# lp_board.net
KiCad netlist of a schematic drawn in EAGLE
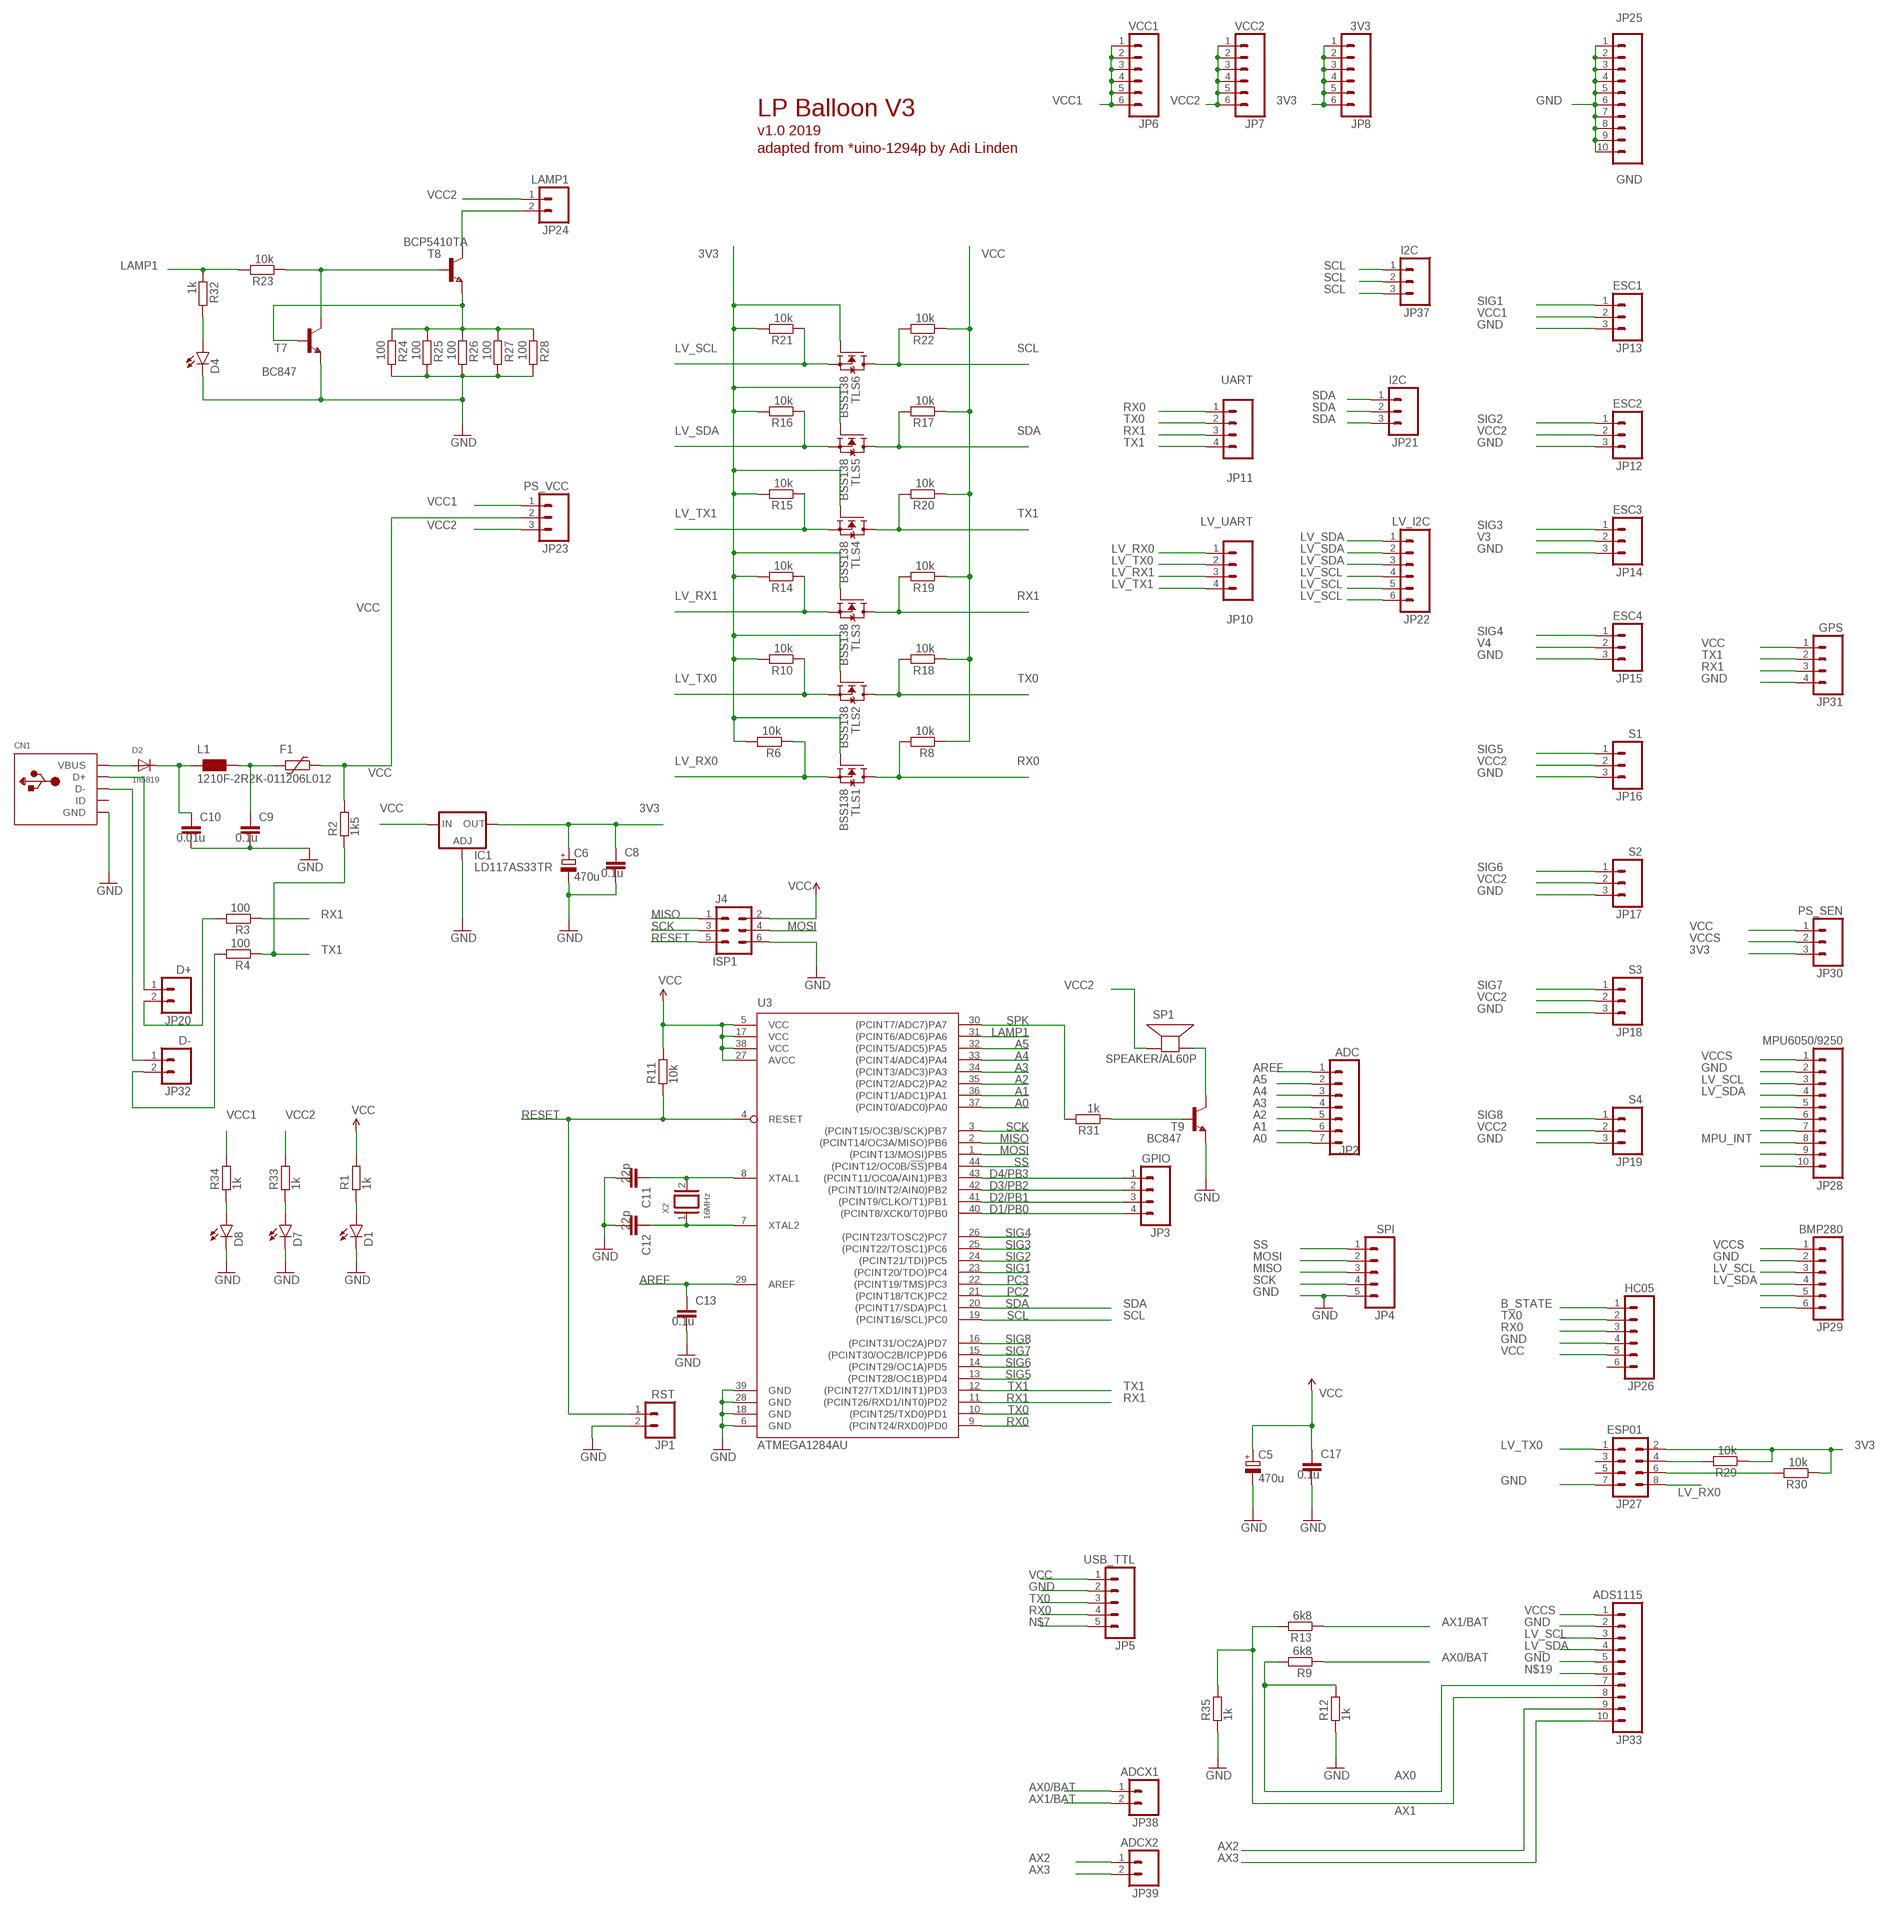
[diagram p0: schematic, sheet 1]

(export (version "E")
  (design (tool "Eeschema 10.0.6"))
  (components
    (comp (ref "C5")
      (value "470u")
      (footprint "eagle-import:E5-10,5")
      (libsource (lib "eagle-import") (part "CPOL-EUE5-10.5"))
    )
    (comp (ref "C6")
      (value "470u")
      (footprint "eagle-import:E5-10,5")
      (libsource (lib "eagle-import") (part "CPOL-EUE5-10.5"))
    )
    (comp (ref "C8")
      (value "0.1u")
      (footprint "eagle-import:C0603")
      (libsource (lib "eagle-import") (part "C-EUC0603"))
    )
    (comp (ref "C9")
      (value "0.1u")
      (footprint "eagle-import:C0603")
      (libsource (lib "eagle-import") (part "C-EUC0603"))
    )
    (comp (ref "C10")
      (value "0.01u")
      (footprint "eagle-import:C0603")
      (libsource (lib "eagle-import") (part "C-EUC0603"))
    )
    (comp (ref "C11")
      (value "22p")
      (footprint "eagle-import:C0603")
      (libsource (lib "eagle-import") (part "C-EUC0603"))
    )
    (comp (ref "C12")
      (value "22p")
      (footprint "eagle-import:C0603")
      (libsource (lib "eagle-import") (part "C-EUC0603"))
    )
    (comp (ref "C13")
      (value "0.1u")
      (footprint "eagle-import:C0603")
      (libsource (lib "eagle-import") (part "C-EUC0603"))
    )
    (comp (ref "C17")
      (value "0.1u")
      (footprint "eagle-import:C0603")
      (libsource (lib "eagle-import") (part "C-EUC0603"))
    )
    (comp (ref "CN1")
      (value "USBMINIB")
      (footprint "eagle-import:USB-MINIB")
      (libsource (lib "eagle-import") (part "USBMINIB"))
    )
    (comp (ref "D1")
      (value "PWR")
      (footprint "eagle-import:SML0805")
      (libsource (lib "eagle-import") (part "LEDSML0805"))
    )
    (comp (ref "D2")
      (value "1n5819")
      (footprint "eagle-import:SOD-123")
      (libsource (lib "eagle-import") (part "DIODESOD-123"))
    )
    (comp (ref "D4")
      (value "LAMP1")
      (footprint "eagle-import:SML0805")
      (libsource (lib "eagle-import") (part "LEDSML0805"))
    )
    (comp (ref "D7")
      (value "PWR2")
      (footprint "eagle-import:SML0805")
      (libsource (lib "eagle-import") (part "LEDSML0805"))
    )
    (comp (ref "D8")
      (value "PWR1")
      (footprint "eagle-import:SML0805")
      (libsource (lib "eagle-import") (part "LEDSML0805"))
    )
    (comp (ref "F1")
      (value "1206L012")
      (footprint "eagle-import:1206L")
      (fields (field (name "MF") "Littelfuse"))
      (libsource (lib "eagle-import") (part "?1206L012"))
    )
    (comp (ref "IC1")
      (value "LD117AS33TR")
      (footprint "eagle-import:SOT223")
      (libsource (lib "eagle-import") (part "LD117A?S33TR"))
    )
    (comp (ref "J4")
      (value "ISP1")
      (footprint "eagle-import:2X03_ROUND")
      (libsource (lib "eagle-import") (part "M03X2-ROUND"))
    )
    (comp (ref "JP1")
      (value "RST")
      (footprint "eagle-import:1X02")
      (libsource (lib "eagle-import") (part "M02PTH"))
    )
    (comp (ref "JP2")
      (value "ADC")
      (footprint "eagle-import:1X07")
      (libsource (lib "eagle-import") (part "M07"))
    )
    (comp (ref "JP3")
      (value "GPIO")
      (footprint "eagle-import:1X04")
      (libsource (lib "eagle-import") (part "M04PTH"))
    )
    (comp (ref "JP4")
      (value "SPI")
      (footprint "eagle-import:1X05")
      (libsource (lib "eagle-import") (part "M05PTH"))
    )
    (comp (ref "JP5")
      (value "USB_TTL")
      (footprint "eagle-import:1X05")
      (libsource (lib "eagle-import") (part "M05PTH"))
    )
    (comp (ref "JP6")
      (value "VCC1")
      (footprint "eagle-import:1X06")
      (libsource (lib "eagle-import") (part "M06SIP"))
    )
    (comp (ref "JP7")
      (value "VCC2")
      (footprint "eagle-import:1X06")
      (libsource (lib "eagle-import") (part "M06SIP"))
    )
    (comp (ref "JP8")
      (value "3V3")
      (footprint "eagle-import:1X06")
      (libsource (lib "eagle-import") (part "M06SIP"))
    )
    (comp (ref "JP10")
      (value "LV_UART")
      (footprint "eagle-import:1X04")
      (libsource (lib "eagle-import") (part "M04PTH"))
    )
    (comp (ref "JP11")
      (value "UART")
      (footprint "eagle-import:1X04")
      (libsource (lib "eagle-import") (part "M04PTH"))
    )
    (comp (ref "JP12")
      (value "ESC2")
      (footprint "eagle-import:1X03")
      (libsource (lib "eagle-import") (part "M03PTH"))
    )
    (comp (ref "JP13")
      (value "ESC1")
      (footprint "eagle-import:1X03")
      (libsource (lib "eagle-import") (part "M03PTH"))
    )
    (comp (ref "JP14")
      (value "ESC3")
      (footprint "eagle-import:1X03")
      (libsource (lib "eagle-import") (part "M03PTH"))
    )
    (comp (ref "JP15")
      (value "ESC4")
      (footprint "eagle-import:1X03")
      (libsource (lib "eagle-import") (part "M03PTH"))
    )
    (comp (ref "JP16")
      (value "S1")
      (footprint "eagle-import:1X03")
      (libsource (lib "eagle-import") (part "M03PTH"))
    )
    (comp (ref "JP17")
      (value "S2")
      (footprint "eagle-import:1X03")
      (libsource (lib "eagle-import") (part "M03PTH"))
    )
    (comp (ref "JP18")
      (value "S3")
      (footprint "eagle-import:1X03")
      (libsource (lib "eagle-import") (part "M03PTH"))
    )
    (comp (ref "JP19")
      (value "S4")
      (footprint "eagle-import:1X03")
      (libsource (lib "eagle-import") (part "M03PTH"))
    )
    (comp (ref "JP20")
      (value "D+")
      (footprint "eagle-import:1X02")
      (libsource (lib "eagle-import") (part "M02PTH"))
    )
    (comp (ref "JP21")
      (value "I2C")
      (footprint "eagle-import:1X03")
      (libsource (lib "eagle-import") (part "M03PTH"))
    )
    (comp (ref "JP22")
      (value "LV_I2C")
      (footprint "eagle-import:1X06")
      (libsource (lib "eagle-import") (part "M06SIP"))
    )
    (comp (ref "JP23")
      (value "PS_VCC")
      (footprint "eagle-import:1X03")
      (libsource (lib "eagle-import") (part "M03PTH"))
    )
    (comp (ref "JP24")
      (value "LAMP1")
      (footprint "eagle-import:1X02")
      (libsource (lib "eagle-import") (part "M02PTH"))
    )
    (comp (ref "JP25")
      (value "GND")
      (footprint "eagle-import:1X10")
      (libsource (lib "eagle-import") (part "M10{dblquote}"))
    )
    (comp (ref "JP26")
      (value "HC05")
      (footprint "eagle-import:1X06")
      (libsource (lib "eagle-import") (part "M06SIP"))
    )
    (comp (ref "JP27")
      (value "ESP01")
      (footprint "eagle-import:MA04-2")
      (libsource (lib "eagle-import") (part "MA04-2"))
    )
    (comp (ref "JP28")
      (value "MPU6050/9250")
      (footprint "eagle-import:1X10")
      (libsource (lib "eagle-import") (part "M10{dblquote}"))
    )
    (comp (ref "JP29")
      (value "BMP280")
      (footprint "eagle-import:1X06")
      (libsource (lib "eagle-import") (part "M06SIP"))
    )
    (comp (ref "JP30")
      (value "PS_SEN")
      (footprint "eagle-import:1X03")
      (libsource (lib "eagle-import") (part "M03PTH"))
    )
    (comp (ref "JP31")
      (value "GPS")
      (footprint "eagle-import:1X04")
      (libsource (lib "eagle-import") (part "M04PTH"))
    )
    (comp (ref "JP32")
      (value "D-")
      (footprint "eagle-import:1X02")
      (libsource (lib "eagle-import") (part "M02PTH"))
    )
    (comp (ref "JP33")
      (value "ADS1115")
      (footprint "eagle-import:1X10")
      (libsource (lib "eagle-import") (part "M10{dblquote}"))
    )
    (comp (ref "JP37")
      (value "I2C")
      (footprint "eagle-import:1X03")
      (libsource (lib "eagle-import") (part "M03PTH"))
    )
    (comp (ref "JP38")
      (value "ADCX1")
      (footprint "eagle-import:1X02")
      (libsource (lib "eagle-import") (part "M02PTH"))
    )
    (comp (ref "JP39")
      (value "ADCX2")
      (footprint "eagle-import:1X02")
      (libsource (lib "eagle-import") (part "M02PTH"))
    )
    (comp (ref "L1")
      (value "1210F-2R2K-01")
      (footprint "eagle-import:1210")
      (libsource (lib "eagle-import") (part "WE-CBF_1210"))
    )
    (comp (ref "R1")
      (value "1k")
      (footprint "eagle-import:R0603")
      (libsource (lib "eagle-import") (part "R-EU_R0603"))
    )
    (comp (ref "R2")
      (value "1k5")
      (footprint "eagle-import:R0603")
      (libsource (lib "eagle-import") (part "R-EU_R0603"))
    )
    (comp (ref "R3")
      (value "100")
      (footprint "eagle-import:R0603")
      (libsource (lib "eagle-import") (part "R-EU_R0603"))
    )
    (comp (ref "R4")
      (value "100")
      (footprint "eagle-import:R0603")
      (libsource (lib "eagle-import") (part "R-EU_R0603"))
    )
    (comp (ref "R6")
      (value "10k")
      (footprint "eagle-import:R0603")
      (libsource (lib "eagle-import") (part "R-EU_R0603"))
    )
    (comp (ref "R8")
      (value "10k")
      (footprint "eagle-import:R0603")
      (libsource (lib "eagle-import") (part "R-EU_R0603"))
    )
    (comp (ref "R9")
      (value "6k8")
      (footprint "eagle-import:R0603")
      (libsource (lib "eagle-import") (part "R-EU_R0603"))
    )
    (comp (ref "R10")
      (value "10k")
      (footprint "eagle-import:R0603")
      (libsource (lib "eagle-import") (part "R-EU_R0603"))
    )
    (comp (ref "R11")
      (value "10k")
      (footprint "eagle-import:R0603")
      (libsource (lib "eagle-import") (part "R-EU_R0603"))
    )
    (comp (ref "R12")
      (value "1k")
      (footprint "eagle-import:R0603")
      (libsource (lib "eagle-import") (part "R-EU_R0603"))
    )
    (comp (ref "R13")
      (value "6k8")
      (footprint "eagle-import:R0603")
      (libsource (lib "eagle-import") (part "R-EU_R0603"))
    )
    (comp (ref "R14")
      (value "10k")
      (footprint "eagle-import:R0603")
      (libsource (lib "eagle-import") (part "R-EU_R0603"))
    )
    (comp (ref "R15")
      (value "10k")
      (footprint "eagle-import:R0603")
      (libsource (lib "eagle-import") (part "R-EU_R0603"))
    )
    (comp (ref "R16")
      (value "10k")
      (footprint "eagle-import:R0603")
      (libsource (lib "eagle-import") (part "R-EU_R0603"))
    )
    (comp (ref "R17")
      (value "10k")
      (footprint "eagle-import:R0603")
      (libsource (lib "eagle-import") (part "R-EU_R0603"))
    )
    (comp (ref "R18")
      (value "10k")
      (footprint "eagle-import:R0603")
      (libsource (lib "eagle-import") (part "R-EU_R0603"))
    )
    (comp (ref "R19")
      (value "10k")
      (footprint "eagle-import:R0603")
      (libsource (lib "eagle-import") (part "R-EU_R0603"))
    )
    (comp (ref "R20")
      (value "10k")
      (footprint "eagle-import:R0603")
      (libsource (lib "eagle-import") (part "R-EU_R0603"))
    )
    (comp (ref "R21")
      (value "10k")
      (footprint "eagle-import:R0603")
      (libsource (lib "eagle-import") (part "R-EU_R0603"))
    )
    (comp (ref "R22")
      (value "10k")
      (footprint "eagle-import:R0603")
      (libsource (lib "eagle-import") (part "R-EU_R0603"))
    )
    (comp (ref "R23")
      (value "10k")
      (footprint "eagle-import:R0603")
      (libsource (lib "eagle-import") (part "R-EU_R0603"))
    )
    (comp (ref "R24")
      (value "100")
      (footprint "eagle-import:R0603")
      (libsource (lib "eagle-import") (part "R-EU_R0603"))
    )
    (comp (ref "R25")
      (value "100")
      (footprint "eagle-import:R0603")
      (libsource (lib "eagle-import") (part "R-EU_R0603"))
    )
    (comp (ref "R26")
      (value "100")
      (footprint "eagle-import:R0603")
      (libsource (lib "eagle-import") (part "R-EU_R0603"))
    )
    (comp (ref "R27")
      (value "100")
      (footprint "eagle-import:R0603")
      (libsource (lib "eagle-import") (part "R-EU_R0603"))
    )
    (comp (ref "R28")
      (value "100")
      (footprint "eagle-import:R0603")
      (libsource (lib "eagle-import") (part "R-EU_R0603"))
    )
    (comp (ref "R29")
      (value "10k")
      (footprint "eagle-import:R0603")
      (libsource (lib "eagle-import") (part "R-EU_R0603"))
    )
    (comp (ref "R30")
      (value "10k")
      (footprint "eagle-import:R0603")
      (libsource (lib "eagle-import") (part "R-EU_R0603"))
    )
    (comp (ref "R31")
      (value "1k")
      (footprint "eagle-import:R0603")
      (libsource (lib "eagle-import") (part "R-EU_R0603"))
    )
    (comp (ref "R32")
      (value "1k")
      (footprint "eagle-import:R0603")
      (libsource (lib "eagle-import") (part "R-EU_R0603"))
    )
    (comp (ref "R33")
      (value "1k")
      (footprint "eagle-import:R0603")
      (libsource (lib "eagle-import") (part "R-EU_R0603"))
    )
    (comp (ref "R34")
      (value "1k")
      (footprint "eagle-import:R0603")
      (libsource (lib "eagle-import") (part "R-EU_R0603"))
    )
    (comp (ref "R35")
      (value "1k")
      (footprint "eagle-import:R0603")
      (libsource (lib "eagle-import") (part "R-EU_R0603"))
    )
    (comp (ref "SP1")
      (value "SPEAKER/AL60P")
      (footprint "eagle-import:AL60P")
      (libsource (lib "eagle-import") (part "SPEAKER/AL60P"))
    )
    (comp (ref "T7")
      (value "BC847")
      (footprint "eagle-import:SOT23")
      (libsource (lib "eagle-import") (part "BC847"))
    )
    (comp (ref "T8")
      (value "BCP5410TA")
      (footprint "eagle-import:SOT223")
      (fields (field (name "MPN") "DJT4031N-13"))
      (libsource (lib "eagle-import") (part "NPNSOT223"))
    )
    (comp (ref "T9")
      (value "BC847")
      (footprint "eagle-import:SOT23")
      (libsource (lib "eagle-import") (part "BC847"))
    )
    (comp (ref "TLS1")
      (value "BSS138")
      (footprint "eagle-import:SOT23")
      (libsource (lib "eagle-import") (part "MOSFET-N-SOT23"))
    )
    (comp (ref "TLS2")
      (value "BSS138")
      (footprint "eagle-import:SOT23")
      (libsource (lib "eagle-import") (part "MOSFET-N-SOT23"))
    )
    (comp (ref "TLS3")
      (value "BSS138")
      (footprint "eagle-import:SOT23")
      (libsource (lib "eagle-import") (part "MOSFET-N-SOT23"))
    )
    (comp (ref "TLS4")
      (value "BSS138")
      (footprint "eagle-import:SOT23")
      (libsource (lib "eagle-import") (part "MOSFET-N-SOT23"))
    )
    (comp (ref "TLS5")
      (value "BSS138")
      (footprint "eagle-import:SOT23")
      (libsource (lib "eagle-import") (part "MOSFET-N-SOT23"))
    )
    (comp (ref "TLS6")
      (value "BSS138")
      (footprint "eagle-import:SOT23")
      (libsource (lib "eagle-import") (part "MOSFET-N-SOT23"))
    )
    (comp (ref "U3")
      (value "ATMEGA1284AU")
      (footprint "eagle-import:TQFP44")
      (fields (field (name "MPN") "ATMEGA644PV-10AU"))
      (libsource (lib "eagle-import") (part "ATMEGA1284P-AU"))
    )
    (comp (ref "X2")
      (value "16MHz")
      (footprint "eagle-import:QS")
      (libsource (lib "eagle-import") (part "XTAL/S"))
    )
  )
  (nets
    (net (code "1") (name "/3V3") (class "Default")
      (node (ref "C6") (pin "+") (pinfunction "+_+") (pintype "passive"))
      (node (ref "C8") (pin "1") (pinfunction "1_1") (pintype "passive"))
      (node (ref "IC1") (pin "4") (pinfunction "OUT_4") (pintype "passive"))
      (node (ref "JP27") (pin "2") (pinfunction "2_2") (pintype "passive"))
      (node (ref "JP30") (pin "3") (pinfunction "3_3") (pintype "passive"))
      (node (ref "JP8") (pin "1") (pinfunction "1_1") (pintype "passive"))
      (node (ref "JP8") (pin "2") (pinfunction "2_2") (pintype "passive"))
      (node (ref "JP8") (pin "3") (pinfunction "3_3") (pintype "passive"))
      (node (ref "JP8") (pin "4") (pinfunction "4_4") (pintype "passive"))
      (node (ref "JP8") (pin "5") (pinfunction "5_5") (pintype "passive"))
      (node (ref "JP8") (pin "6") (pinfunction "6_6") (pintype "passive"))
      (node (ref "R10") (pin "2") (pinfunction "2_2") (pintype "passive"))
      (node (ref "R14") (pin "2") (pinfunction "2_2") (pintype "passive"))
      (node (ref "R15") (pin "2") (pinfunction "2_2") (pintype "passive"))
      (node (ref "R16") (pin "2") (pinfunction "2_2") (pintype "passive"))
      (node (ref "R21") (pin "2") (pinfunction "2_2") (pintype "passive"))
      (node (ref "R29") (pin "1") (pinfunction "1_1") (pintype "passive"))
      (node (ref "R30") (pin "1") (pinfunction "1_1") (pintype "passive"))
      (node (ref "R6") (pin "2") (pinfunction "2_2") (pintype "passive"))
      (node (ref "TLS1") (pin "1") (pinfunction "G_1") (pintype "passive"))
      (node (ref "TLS2") (pin "1") (pinfunction "G_1") (pintype "passive"))
      (node (ref "TLS3") (pin "1") (pinfunction "G_1") (pintype "passive"))
      (node (ref "TLS4") (pin "1") (pinfunction "G_1") (pintype "passive"))
      (node (ref "TLS5") (pin "1") (pinfunction "G_1") (pintype "passive"))
      (node (ref "TLS6") (pin "1") (pinfunction "G_1") (pintype "passive"))
    )
    (net (code "2") (name "/A0") (class "Default")
      (node (ref "JP2") (pin "7") (pinfunction "7_7") (pintype "passive"))
      (node (ref "U3") (pin "37") (pinfunction "(PCINT0/ADC0)PA0_37") (pintype "bidirectional"))
    )
    (net (code "3") (name "/A1") (class "Default")
      (node (ref "JP2") (pin "6") (pinfunction "6_6") (pintype "passive"))
      (node (ref "U3") (pin "36") (pinfunction "(PCINT1/ADC1)PA1_36") (pintype "bidirectional"))
    )
    (net (code "4") (name "/A2") (class "Default")
      (node (ref "JP2") (pin "5") (pinfunction "5_5") (pintype "passive"))
      (node (ref "U3") (pin "35") (pinfunction "(PCINT2/ADC2)PA2_35") (pintype "bidirectional"))
    )
    (net (code "5") (name "/A3") (class "Default")
      (node (ref "JP2") (pin "4") (pinfunction "4_4") (pintype "passive"))
      (node (ref "U3") (pin "34") (pinfunction "(PCINT3/ADC3)PA3_34") (pintype "bidirectional"))
    )
    (net (code "6") (name "/A4") (class "Default")
      (node (ref "JP2") (pin "3") (pinfunction "3_3") (pintype "passive"))
      (node (ref "U3") (pin "33") (pinfunction "(PCINT4/ADC4)PA4_33") (pintype "bidirectional"))
    )
    (net (code "7") (name "/A5") (class "Default")
      (node (ref "JP2") (pin "2") (pinfunction "2_2") (pintype "passive"))
      (node (ref "U3") (pin "32") (pinfunction "(PCINT5/ADC5)PA5_32") (pintype "bidirectional"))
    )
    (net (code "8") (name "/AREF") (class "Default")
      (node (ref "C13") (pin "1") (pinfunction "1_1") (pintype "passive"))
      (node (ref "JP2") (pin "1") (pinfunction "1_1") (pintype "passive"))
      (node (ref "U3") (pin "29") (pinfunction "AREF_29") (pintype "passive"))
    )
    (net (code "9") (name "/AX0") (class "Default")
      (node (ref "JP33") (pin "7") (pinfunction "7_7") (pintype "passive"))
      (node (ref "R12") (pin "2") (pinfunction "2_2") (pintype "passive"))
      (node (ref "R9") (pin "2") (pinfunction "2_2") (pintype "passive"))
    )
    (net (code "10") (name "/AX0{slash}BAT") (class "Default")
      (node (ref "JP38") (pin "1") (pinfunction "1_1") (pintype "passive"))
      (node (ref "R9") (pin "1") (pinfunction "1_1") (pintype "passive"))
    )
    (net (code "11") (name "/AX1") (class "Default")
      (node (ref "JP33") (pin "8") (pinfunction "8_8") (pintype "passive"))
      (node (ref "R13") (pin "2") (pinfunction "2_2") (pintype "passive"))
      (node (ref "R35") (pin "2") (pinfunction "2_2") (pintype "passive"))
    )
    (net (code "12") (name "/AX1{slash}BAT") (class "Default")
      (node (ref "JP38") (pin "2") (pinfunction "2_2") (pintype "passive"))
      (node (ref "R13") (pin "1") (pinfunction "1_1") (pintype "passive"))
    )
    (net (code "13") (name "/AX2") (class "Default")
      (node (ref "JP33") (pin "9") (pinfunction "9_9") (pintype "passive"))
      (node (ref "JP39") (pin "1") (pinfunction "1_1") (pintype "passive"))
    )
    (net (code "14") (name "/AX3") (class "Default")
      (node (ref "JP33") (pin "10") (pinfunction "10_10") (pintype "passive"))
      (node (ref "JP39") (pin "2") (pinfunction "2_2") (pintype "passive"))
    )
    (net (code "15") (name "/B_STATE") (class "Default")
      (node (ref "JP26") (pin "1") (pinfunction "1_1") (pintype "passive"))
    )
    (net (code "16") (name "/D1{slash}PB0") (class "Default")
      (node (ref "JP3") (pin "4") (pinfunction "4_4") (pintype "passive"))
      (node (ref "U3") (pin "40") (pinfunction "(PCINT8/XCK0/T0)PB0_40") (pintype "bidirectional"))
    )
    (net (code "17") (name "/D2{slash}PB1") (class "Default")
      (node (ref "JP3") (pin "3") (pinfunction "3_3") (pintype "passive"))
      (node (ref "U3") (pin "41") (pinfunction "(PCINT9/CLKO/T1)PB1_41") (pintype "bidirectional"))
    )
    (net (code "18") (name "/D3{slash}PB2") (class "Default")
      (node (ref "JP3") (pin "2") (pinfunction "2_2") (pintype "passive"))
      (node (ref "U3") (pin "42") (pinfunction "(PCINT10/INT2/AIN0)PB2_42") (pintype "bidirectional"))
    )
    (net (code "19") (name "/D4{slash}PB3") (class "Default")
      (node (ref "JP3") (pin "1") (pinfunction "1_1") (pintype "passive"))
      (node (ref "U3") (pin "43") (pinfunction "(PCINT11/OC0A/AIN1)PB3_43") (pintype "bidirectional"))
    )
    (net (code "20") (name "/LAMP1") (class "Default")
      (node (ref "R23") (pin "2") (pinfunction "2_2") (pintype "passive"))
      (node (ref "R32") (pin "1") (pinfunction "1_1") (pintype "passive"))
      (node (ref "U3") (pin "31") (pinfunction "(PCINT6/ADC6)PA6_31") (pintype "bidirectional"))
    )
    (net (code "21") (name "/LV_RX0") (class "Default")
      (node (ref "JP10") (pin "1") (pinfunction "1_1") (pintype "passive"))
      (node (ref "JP27") (pin "8") (pinfunction "8_8") (pintype "passive"))
      (node (ref "R6") (pin "1") (pinfunction "1_1") (pintype "passive"))
      (node (ref "TLS1") (pin "2") (pinfunction "S_2") (pintype "passive"))
    )
    (net (code "22") (name "/LV_RX1") (class "Default")
      (node (ref "JP10") (pin "3") (pinfunction "3_3") (pintype "passive"))
      (node (ref "R14") (pin "1") (pinfunction "1_1") (pintype "passive"))
      (node (ref "TLS3") (pin "2") (pinfunction "S_2") (pintype "passive"))
    )
    (net (code "23") (name "/LV_SCL") (class "Default")
      (node (ref "JP22") (pin "4") (pinfunction "4_4") (pintype "passive"))
      (node (ref "JP22") (pin "5") (pinfunction "5_5") (pintype "passive"))
      (node (ref "JP22") (pin "6") (pinfunction "6_6") (pintype "passive"))
      (node (ref "JP28") (pin "3") (pinfunction "3_3") (pintype "passive"))
      (node (ref "JP29") (pin "3") (pinfunction "3_3") (pintype "passive"))
      (node (ref "JP33") (pin "3") (pinfunction "3_3") (pintype "passive"))
      (node (ref "R21") (pin "1") (pinfunction "1_1") (pintype "passive"))
      (node (ref "TLS6") (pin "2") (pinfunction "S_2") (pintype "passive"))
    )
    (net (code "24") (name "/LV_SDA") (class "Default")
      (node (ref "JP22") (pin "1") (pinfunction "1_1") (pintype "passive"))
      (node (ref "JP22") (pin "2") (pinfunction "2_2") (pintype "passive"))
      (node (ref "JP22") (pin "3") (pinfunction "3_3") (pintype "passive"))
      (node (ref "JP28") (pin "4") (pinfunction "4_4") (pintype "passive"))
      (node (ref "JP29") (pin "4") (pinfunction "4_4") (pintype "passive"))
      (node (ref "JP33") (pin "4") (pinfunction "4_4") (pintype "passive"))
      (node (ref "R16") (pin "1") (pinfunction "1_1") (pintype "passive"))
      (node (ref "TLS5") (pin "2") (pinfunction "S_2") (pintype "passive"))
    )
    (net (code "25") (name "/LV_TX0") (class "Default")
      (node (ref "JP10") (pin "2") (pinfunction "2_2") (pintype "passive"))
      (node (ref "JP27") (pin "1") (pinfunction "1_1") (pintype "passive"))
      (node (ref "R10") (pin "1") (pinfunction "1_1") (pintype "passive"))
      (node (ref "TLS2") (pin "2") (pinfunction "S_2") (pintype "passive"))
    )
    (net (code "26") (name "/LV_TX1") (class "Default")
      (node (ref "JP10") (pin "4") (pinfunction "4_4") (pintype "passive"))
      (node (ref "R15") (pin "1") (pinfunction "1_1") (pintype "passive"))
      (node (ref "TLS4") (pin "2") (pinfunction "S_2") (pintype "passive"))
    )
    (net (code "27") (name "/MISO") (class "Default")
      (node (ref "J4") (pin "1") (pinfunction "1_1") (pintype "passive"))
      (node (ref "JP4") (pin "3") (pinfunction "3_3") (pintype "passive"))
      (node (ref "U3") (pin "2") (pinfunction "(PCINT14/OC3A/MISO)PB6_2") (pintype "bidirectional"))
    )
    (net (code "28") (name "/MOSI") (class "Default")
      (node (ref "J4") (pin "4") (pinfunction "4_4") (pintype "passive"))
      (node (ref "JP4") (pin "2") (pinfunction "2_2") (pintype "passive"))
      (node (ref "U3") (pin "1") (pinfunction "(PCINT13/MOSI)PB5_1") (pintype "bidirectional"))
    )
    (net (code "29") (name "/MPU_INT") (class "Default")
      (node (ref "JP28") (pin "8") (pinfunction "8_8") (pintype "passive"))
    )
    (net (code "30") (name "/N$7") (class "Default")
      (node (ref "JP5") (pin "5") (pinfunction "5_5") (pintype "passive"))
    )
    (net (code "31") (name "/N$19") (class "Default")
      (node (ref "JP33") (pin "6") (pinfunction "6_6") (pintype "passive"))
    )
    (net (code "32") (name "/PC2") (class "Default")
      (node (ref "U3") (pin "21") (pinfunction "(PCINT18/TCK)PC2_21") (pintype "output"))
    )
    (net (code "33") (name "/PC3") (class "Default")
      (node (ref "U3") (pin "22") (pinfunction "(PCINT19/TMS)PC3_22") (pintype "output"))
    )
    (net (code "34") (name "/RESET") (class "Default")
      (node (ref "J4") (pin "5") (pinfunction "5_5") (pintype "passive"))
      (node (ref "JP1") (pin "1") (pinfunction "1_1") (pintype "passive"))
      (node (ref "R11") (pin "1") (pinfunction "1_1") (pintype "passive"))
      (node (ref "U3") (pin "4") (pinfunction "RESET_4") (pintype "input"))
    )
    (net (code "35") (name "/RX0") (class "Default")
      (node (ref "JP11") (pin "1") (pinfunction "1_1") (pintype "passive"))
      (node (ref "JP26") (pin "3") (pinfunction "3_3") (pintype "passive"))
      (node (ref "JP5") (pin "4") (pinfunction "4_4") (pintype "passive"))
      (node (ref "R8") (pin "2") (pinfunction "2_2") (pintype "passive"))
      (node (ref "TLS1") (pin "3") (pinfunction "D_3") (pintype "passive"))
      (node (ref "U3") (pin "9") (pinfunction "(PCINT24/RXD0)PD0_9") (pintype "bidirectional"))
    )
    (net (code "36") (name "/RX1") (class "Default")
      (node (ref "JP11") (pin "3") (pinfunction "3_3") (pintype "passive"))
      (node (ref "JP31") (pin "3") (pinfunction "3_3") (pintype "passive"))
      (node (ref "R19") (pin "2") (pinfunction "2_2") (pintype "passive"))
      (node (ref "R3") (pin "1") (pinfunction "1_1") (pintype "passive"))
      (node (ref "TLS3") (pin "3") (pinfunction "D_3") (pintype "passive"))
      (node (ref "U3") (pin "11") (pinfunction "(PCINT26/RXD1/INT0)PD2_11") (pintype "bidirectional"))
    )
    (net (code "37") (name "/SCK") (class "Default")
      (node (ref "J4") (pin "3") (pinfunction "3_3") (pintype "passive"))
      (node (ref "JP4") (pin "4") (pinfunction "4_4") (pintype "passive"))
      (node (ref "U3") (pin "3") (pinfunction "(PCINT15/OC3B/SCK)PB7_3") (pintype "bidirectional"))
    )
    (net (code "38") (name "/SCL") (class "Default")
      (node (ref "JP37") (pin "1") (pinfunction "1_1") (pintype "passive"))
      (node (ref "JP37") (pin "2") (pinfunction "2_2") (pintype "passive"))
      (node (ref "JP37") (pin "3") (pinfunction "3_3") (pintype "passive"))
      (node (ref "R22") (pin "2") (pinfunction "2_2") (pintype "passive"))
      (node (ref "TLS6") (pin "3") (pinfunction "D_3") (pintype "passive"))
      (node (ref "U3") (pin "19") (pinfunction "(PCINT16/SCL)PC0_19") (pintype "output"))
    )
    (net (code "39") (name "/SDA") (class "Default")
      (node (ref "JP21") (pin "1") (pinfunction "1_1") (pintype "passive"))
      (node (ref "JP21") (pin "2") (pinfunction "2_2") (pintype "passive"))
      (node (ref "JP21") (pin "3") (pinfunction "3_3") (pintype "passive"))
      (node (ref "R17") (pin "2") (pinfunction "2_2") (pintype "passive"))
      (node (ref "TLS5") (pin "3") (pinfunction "D_3") (pintype "passive"))
      (node (ref "U3") (pin "20") (pinfunction "(PCINT17/SDA)PC1_20") (pintype "output"))
    )
    (net (code "40") (name "/SIG1") (class "Default")
      (node (ref "JP13") (pin "1") (pinfunction "1_1") (pintype "passive"))
      (node (ref "U3") (pin "23") (pinfunction "(PCINT20/TDO)PC4_23") (pintype "output"))
    )
    (net (code "41") (name "/SIG2") (class "Default")
      (node (ref "JP12") (pin "1") (pinfunction "1_1") (pintype "passive"))
      (node (ref "U3") (pin "24") (pinfunction "(PCINT21/TDI)PC5_24") (pintype "output"))
    )
    (net (code "42") (name "/SIG3") (class "Default")
      (node (ref "JP14") (pin "1") (pinfunction "1_1") (pintype "passive"))
      (node (ref "U3") (pin "25") (pinfunction "(PCINT22/TOSC1)PC6_25") (pintype "output"))
    )
    (net (code "43") (name "/SIG4") (class "Default")
      (node (ref "JP15") (pin "1") (pinfunction "1_1") (pintype "passive"))
      (node (ref "U3") (pin "26") (pinfunction "(PCINT23/TOSC2)PC7_26") (pintype "output"))
    )
    (net (code "44") (name "/SIG5") (class "Default")
      (node (ref "JP16") (pin "1") (pinfunction "1_1") (pintype "passive"))
      (node (ref "U3") (pin "13") (pinfunction "(PCINT28/OC1B)PD4_13") (pintype "bidirectional"))
    )
    (net (code "45") (name "/SIG6") (class "Default")
      (node (ref "JP17") (pin "1") (pinfunction "1_1") (pintype "passive"))
      (node (ref "U3") (pin "14") (pinfunction "(PCINT29/OC1A)PD5_14") (pintype "bidirectional"))
    )
    (net (code "46") (name "/SIG7") (class "Default")
      (node (ref "JP18") (pin "1") (pinfunction "1_1") (pintype "passive"))
      (node (ref "U3") (pin "15") (pinfunction "(PCINT30/OC2B/ICP)PD6_15") (pintype "bidirectional"))
    )
    (net (code "47") (name "/SIG8") (class "Default")
      (node (ref "JP19") (pin "1") (pinfunction "1_1") (pintype "passive"))
      (node (ref "U3") (pin "16") (pinfunction "(PCINT31/OC2A)PD7_16") (pintype "bidirectional"))
    )
    (net (code "48") (name "/SPK") (class "Default")
      (node (ref "R31") (pin "2") (pinfunction "2_2") (pintype "passive"))
      (node (ref "U3") (pin "30") (pinfunction "(PCINT7/ADC7)PA7_30") (pintype "bidirectional"))
    )
    (net (code "49") (name "/SS") (class "Default")
      (node (ref "JP4") (pin "1") (pinfunction "1_1") (pintype "passive"))
      (node (ref "U3") (pin "44") (pinfunction "(PCINT12/OC0B/~{SS})PB4_44") (pintype "bidirectional"))
    )
    (net (code "50") (name "/TX0") (class "Default")
      (node (ref "JP11") (pin "2") (pinfunction "2_2") (pintype "passive"))
      (node (ref "JP26") (pin "2") (pinfunction "2_2") (pintype "passive"))
      (node (ref "JP5") (pin "3") (pinfunction "3_3") (pintype "passive"))
      (node (ref "R18") (pin "2") (pinfunction "2_2") (pintype "passive"))
      (node (ref "TLS2") (pin "3") (pinfunction "D_3") (pintype "passive"))
      (node (ref "U3") (pin "10") (pinfunction "(PCINT25/TXD0)PD1_10") (pintype "bidirectional"))
    )
    (net (code "51") (name "/TX1") (class "Default")
      (node (ref "JP11") (pin "4") (pinfunction "4_4") (pintype "passive"))
      (node (ref "JP31") (pin "2") (pinfunction "2_2") (pintype "passive"))
      (node (ref "R2") (pin "1") (pinfunction "1_1") (pintype "passive"))
      (node (ref "R20") (pin "2") (pinfunction "2_2") (pintype "passive"))
      (node (ref "R4") (pin "1") (pinfunction "1_1") (pintype "passive"))
      (node (ref "TLS4") (pin "3") (pinfunction "D_3") (pintype "passive"))
      (node (ref "U3") (pin "12") (pinfunction "(PCINT27/TXD1/INT1)PD3_12") (pintype "bidirectional"))
    )
    (net (code "52") (name "/V3") (class "Default")
      (node (ref "JP14") (pin "2") (pinfunction "2_2") (pintype "passive"))
    )
    (net (code "53") (name "/V4") (class "Default")
      (node (ref "JP15") (pin "2") (pinfunction "2_2") (pintype "passive"))
    )
    (net (code "54") (name "/VCC1") (class "Default")
      (node (ref "JP13") (pin "2") (pinfunction "2_2") (pintype "passive"))
      (node (ref "JP23") (pin "1") (pinfunction "1_1") (pintype "passive"))
      (node (ref "JP6") (pin "1") (pinfunction "1_1") (pintype "passive"))
      (node (ref "JP6") (pin "2") (pinfunction "2_2") (pintype "passive"))
      (node (ref "JP6") (pin "3") (pinfunction "3_3") (pintype "passive"))
      (node (ref "JP6") (pin "4") (pinfunction "4_4") (pintype "passive"))
      (node (ref "JP6") (pin "5") (pinfunction "5_5") (pintype "passive"))
      (node (ref "JP6") (pin "6") (pinfunction "6_6") (pintype "passive"))
      (node (ref "R34") (pin "2") (pinfunction "2_2") (pintype "passive"))
    )
    (net (code "55") (name "/VCC2") (class "Default")
      (node (ref "JP12") (pin "2") (pinfunction "2_2") (pintype "passive"))
      (node (ref "JP16") (pin "2") (pinfunction "2_2") (pintype "passive"))
      (node (ref "JP17") (pin "2") (pinfunction "2_2") (pintype "passive"))
      (node (ref "JP18") (pin "2") (pinfunction "2_2") (pintype "passive"))
      (node (ref "JP19") (pin "2") (pinfunction "2_2") (pintype "passive"))
      (node (ref "JP23") (pin "3") (pinfunction "3_3") (pintype "passive"))
      (node (ref "JP24") (pin "1") (pinfunction "1_1") (pintype "passive"))
      (node (ref "JP7") (pin "1") (pinfunction "1_1") (pintype "passive"))
      (node (ref "JP7") (pin "2") (pinfunction "2_2") (pintype "passive"))
      (node (ref "JP7") (pin "3") (pinfunction "3_3") (pintype "passive"))
      (node (ref "JP7") (pin "4") (pinfunction "4_4") (pintype "passive"))
      (node (ref "JP7") (pin "5") (pinfunction "5_5") (pintype "passive"))
      (node (ref "JP7") (pin "6") (pinfunction "6_6") (pintype "passive"))
      (node (ref "R33") (pin "2") (pinfunction "2_2") (pintype "passive"))
      (node (ref "SP1") (pin "1") (pinfunction "+_1") (pintype "passive"))
    )
    (net (code "56") (name "/VCCS") (class "Default")
      (node (ref "JP28") (pin "1") (pinfunction "1_1") (pintype "passive"))
      (node (ref "JP29") (pin "1") (pinfunction "1_1") (pintype "passive"))
      (node (ref "JP30") (pin "2") (pinfunction "2_2") (pintype "passive"))
      (node (ref "JP33") (pin "1") (pinfunction "1_1") (pintype "passive"))
    )
    (net (code "57") (name "GND") (class "Default")
      (node (ref "C10") (pin "2") (pinfunction "2_2") (pintype "passive"))
      (node (ref "C11") (pin "2") (pinfunction "2_2") (pintype "passive"))
      (node (ref "C12") (pin "2") (pinfunction "2_2") (pintype "passive"))
      (node (ref "C13") (pin "2") (pinfunction "2_2") (pintype "passive"))
      (node (ref "C17") (pin "2") (pinfunction "2_2") (pintype "passive"))
      (node (ref "C5") (pin "-") (pinfunction "-_-") (pintype "passive"))
      (node (ref "C6") (pin "-") (pinfunction "-_-") (pintype "passive"))
      (node (ref "C8") (pin "2") (pinfunction "2_2") (pintype "passive"))
      (node (ref "C9") (pin "2") (pinfunction "2_2") (pintype "passive"))
      (node (ref "CN1") (pin "GND") (pinfunction "GND_GND") (pintype "power_in"))
      (node (ref "D1") (pin "C") (pinfunction "C_C") (pintype "passive"))
      (node (ref "D4") (pin "C") (pinfunction "C_C") (pintype "passive"))
      (node (ref "D7") (pin "C") (pinfunction "C_C") (pintype "passive"))
      (node (ref "D8") (pin "C") (pinfunction "C_C") (pintype "passive"))
      (node (ref "IC1") (pin "1") (pinfunction "ADJ_1") (pintype "input"))
      (node (ref "J4") (pin "6") (pinfunction "6_6") (pintype "passive"))
      (node (ref "JP1") (pin "2") (pinfunction "2_2") (pintype "passive"))
      (node (ref "JP12") (pin "3") (pinfunction "3_3") (pintype "passive"))
      (node (ref "JP13") (pin "3") (pinfunction "3_3") (pintype "passive"))
      (node (ref "JP14") (pin "3") (pinfunction "3_3") (pintype "passive"))
      (node (ref "JP15") (pin "3") (pinfunction "3_3") (pintype "passive"))
      (node (ref "JP16") (pin "3") (pinfunction "3_3") (pintype "passive"))
      (node (ref "JP17") (pin "3") (pinfunction "3_3") (pintype "passive"))
      (node (ref "JP18") (pin "3") (pinfunction "3_3") (pintype "passive"))
      (node (ref "JP19") (pin "3") (pinfunction "3_3") (pintype "passive"))
      (node (ref "JP25") (pin "1") (pinfunction "1_1") (pintype "passive"))
      (node (ref "JP25") (pin "10") (pinfunction "10_10") (pintype "passive"))
      (node (ref "JP25") (pin "2") (pinfunction "2_2") (pintype "passive"))
      (node (ref "JP25") (pin "3") (pinfunction "3_3") (pintype "passive"))
      (node (ref "JP25") (pin "4") (pinfunction "4_4") (pintype "passive"))
      (node (ref "JP25") (pin "5") (pinfunction "5_5") (pintype "passive"))
      (node (ref "JP25") (pin "6") (pinfunction "6_6") (pintype "passive"))
      (node (ref "JP25") (pin "7") (pinfunction "7_7") (pintype "passive"))
      (node (ref "JP25") (pin "8") (pinfunction "8_8") (pintype "passive"))
      (node (ref "JP25") (pin "9") (pinfunction "9_9") (pintype "passive"))
      (node (ref "JP26") (pin "4") (pinfunction "4_4") (pintype "passive"))
      (node (ref "JP27") (pin "7") (pinfunction "7_7") (pintype "passive"))
      (node (ref "JP28") (pin "2") (pinfunction "2_2") (pintype "passive"))
      (node (ref "JP29") (pin "2") (pinfunction "2_2") (pintype "passive"))
      (node (ref "JP31") (pin "4") (pinfunction "4_4") (pintype "passive"))
      (node (ref "JP33") (pin "2") (pinfunction "2_2") (pintype "passive"))
      (node (ref "JP33") (pin "5") (pinfunction "5_5") (pintype "passive"))
      (node (ref "JP4") (pin "5") (pinfunction "5_5") (pintype "passive"))
      (node (ref "JP5") (pin "2") (pinfunction "2_2") (pintype "passive"))
      (node (ref "R12") (pin "1") (pinfunction "1_1") (pintype "passive"))
      (node (ref "R24") (pin "2") (pinfunction "2_2") (pintype "passive"))
      (node (ref "R25") (pin "2") (pinfunction "2_2") (pintype "passive"))
      (node (ref "R26") (pin "2") (pinfunction "2_2") (pintype "passive"))
      (node (ref "R27") (pin "2") (pinfunction "2_2") (pintype "passive"))
      (node (ref "R28") (pin "2") (pinfunction "2_2") (pintype "passive"))
      (node (ref "R35") (pin "1") (pinfunction "1_1") (pintype "passive"))
      (node (ref "T7") (pin "2") (pinfunction "E_2") (pintype "passive"))
      (node (ref "T9") (pin "2") (pinfunction "E_2") (pintype "passive"))
      (node (ref "U3") (pin "18") (pinfunction "GND_18") (pintype "power_in"))
      (node (ref "U3") (pin "28") (pinfunction "GND_28") (pintype "power_in"))
      (node (ref "U3") (pin "39") (pinfunction "GND_39") (pintype "power_in"))
      (node (ref "U3") (pin "6") (pinfunction "GND_6") (pintype "power_in"))
    )
    (net (code "58") (name "Net-(C9-Pad1)") (class "Default")
      (node (ref "C9") (pin "1") (pinfunction "1_1") (pintype "passive"))
      (node (ref "F1") (pin "2") (pinfunction "2_2") (pintype "passive"))
      (node (ref "L1") (pin "2") (pinfunction "2_2") (pintype "passive"))
    )
    (net (code "59") (name "Net-(C10-Pad1)") (class "Default")
      (node (ref "C10") (pin "1") (pinfunction "1_1") (pintype "passive"))
      (node (ref "D2") (pin "C") (pinfunction "C_C") (pintype "passive"))
      (node (ref "L1") (pin "1") (pinfunction "1_1") (pintype "passive"))
    )
    (net (code "60") (name "Net-(CN1-PadD+)") (class "Default")
      (node (ref "CN1") (pin "D+") (pinfunction "D+_D+") (pintype "bidirectional"))
      (node (ref "JP20") (pin "1") (pinfunction "1_1") (pintype "passive"))
    )
    (net (code "61") (name "Net-(CN1-PadD-)") (class "Default")
      (node (ref "CN1") (pin "D-") (pinfunction "D-_D-") (pintype "bidirectional"))
      (node (ref "JP32") (pin "1") (pinfunction "1_1") (pintype "passive"))
    )
    (net (code "62") (name "Net-(CN1-PadVBUS)") (class "Default")
      (node (ref "CN1") (pin "VBUS") (pinfunction "VBUS_VBUS") (pintype "power_in"))
      (node (ref "D2") (pin "A") (pinfunction "A_A") (pintype "passive"))
    )
    (net (code "63") (name "Net-(D1-PadA)") (class "Default")
      (node (ref "D1") (pin "A") (pinfunction "A_A") (pintype "passive"))
      (node (ref "R1") (pin "1") (pinfunction "1_1") (pintype "passive"))
    )
    (net (code "64") (name "Net-(D4-PadA)") (class "Default")
      (node (ref "D4") (pin "A") (pinfunction "A_A") (pintype "passive"))
      (node (ref "R32") (pin "2") (pinfunction "2_2") (pintype "passive"))
    )
    (net (code "65") (name "Net-(D7-PadA)") (class "Default")
      (node (ref "D7") (pin "A") (pinfunction "A_A") (pintype "passive"))
      (node (ref "R33") (pin "1") (pinfunction "1_1") (pintype "passive"))
    )
    (net (code "66") (name "Net-(D8-PadA)") (class "Default")
      (node (ref "D8") (pin "A") (pinfunction "A_A") (pintype "passive"))
      (node (ref "R34") (pin "1") (pinfunction "1_1") (pintype "passive"))
    )
    (net (code "67") (name "Net-(JP20-Pad2)") (class "Default")
      (node (ref "JP20") (pin "2") (pinfunction "2_2") (pintype "passive"))
      (node (ref "R3") (pin "2") (pinfunction "2_2") (pintype "passive"))
    )
    (net (code "68") (name "Net-(JP24-Pad2)") (class "Default")
      (node (ref "JP24") (pin "2") (pinfunction "2_2") (pintype "passive"))
      (node (ref "T8") (pin "2") (pinfunction "C_2") (pintype "passive"))
      (node (ref "T8") (pin "4") (pinfunction "C_4") (pintype "passive"))
    )
    (net (code "69") (name "Net-(JP27-Pad4)") (class "Default")
      (node (ref "JP27") (pin "4") (pinfunction "4_4") (pintype "passive"))
      (node (ref "R29") (pin "2") (pinfunction "2_2") (pintype "passive"))
    )
    (net (code "70") (name "Net-(JP27-Pad6)") (class "Default")
      (node (ref "JP27") (pin "6") (pinfunction "6_6") (pintype "passive"))
      (node (ref "R30") (pin "2") (pinfunction "2_2") (pintype "passive"))
    )
    (net (code "71") (name "Net-(JP32-Pad2)") (class "Default")
      (node (ref "JP32") (pin "2") (pinfunction "2_2") (pintype "passive"))
      (node (ref "R4") (pin "2") (pinfunction "2_2") (pintype "passive"))
    )
    (net (code "72") (name "Net-(SP1--)") (class "Default")
      (node (ref "SP1") (pin "2") (pinfunction "-_2") (pintype "passive"))
      (node (ref "T9") (pin "3") (pinfunction "C_3") (pintype "passive"))
    )
    (net (code "73") (name "Net-(T7-B)") (class "Default")
      (node (ref "R24") (pin "1") (pinfunction "1_1") (pintype "passive"))
      (node (ref "R25") (pin "1") (pinfunction "1_1") (pintype "passive"))
      (node (ref "R26") (pin "1") (pinfunction "1_1") (pintype "passive"))
      (node (ref "R27") (pin "1") (pinfunction "1_1") (pintype "passive"))
      (node (ref "R28") (pin "1") (pinfunction "1_1") (pintype "passive"))
      (node (ref "T7") (pin "1") (pinfunction "B_1") (pintype "passive"))
      (node (ref "T8") (pin "3") (pinfunction "E_3") (pintype "passive"))
    )
    (net (code "74") (name "Net-(T7-C)") (class "Default")
      (node (ref "R23") (pin "1") (pinfunction "1_1") (pintype "passive"))
      (node (ref "T7") (pin "3") (pinfunction "C_3") (pintype "passive"))
      (node (ref "T8") (pin "1") (pinfunction "B_1") (pintype "passive"))
    )
    (net (code "75") (name "Net-(T9-B)") (class "Default")
      (node (ref "R31") (pin "1") (pinfunction "1_1") (pintype "passive"))
      (node (ref "T9") (pin "1") (pinfunction "B_1") (pintype "passive"))
    )
    (net (code "76") (name "Net-(U3-XTAL1)") (class "Default")
      (node (ref "C11") (pin "1") (pinfunction "1_1") (pintype "passive"))
      (node (ref "U3") (pin "8") (pinfunction "XTAL1_8") (pintype "bidirectional"))
      (node (ref "X2") (pin "2") (pinfunction "2_2") (pintype "passive"))
    )
    (net (code "77") (name "Net-(U3-XTAL2)") (class "Default")
      (node (ref "C12") (pin "1") (pinfunction "1_1") (pintype "passive"))
      (node (ref "U3") (pin "7") (pinfunction "XTAL2_7") (pintype "bidirectional"))
      (node (ref "X2") (pin "1") (pinfunction "1_1") (pintype "passive"))
    )
    (net (code "78") (name "VCC") (class "Default")
      (node (ref "C17") (pin "1") (pinfunction "1_1") (pintype "passive"))
      (node (ref "C5") (pin "+") (pinfunction "+_+") (pintype "passive"))
      (node (ref "F1") (pin "1") (pinfunction "1_1") (pintype "passive"))
      (node (ref "IC1") (pin "3") (pinfunction "IN_3") (pintype "input"))
      (node (ref "J4") (pin "2") (pinfunction "2_2") (pintype "passive"))
      (node (ref "JP23") (pin "2") (pinfunction "2_2") (pintype "passive"))
      (node (ref "JP26") (pin "5") (pinfunction "5_5") (pintype "passive"))
      (node (ref "JP30") (pin "1") (pinfunction "1_1") (pintype "passive"))
      (node (ref "JP31") (pin "1") (pinfunction "1_1") (pintype "passive"))
      (node (ref "JP5") (pin "1") (pinfunction "1_1") (pintype "passive"))
      (node (ref "R1") (pin "2") (pinfunction "2_2") (pintype "passive"))
      (node (ref "R11") (pin "2") (pinfunction "2_2") (pintype "passive"))
      (node (ref "R17") (pin "1") (pinfunction "1_1") (pintype "passive"))
      (node (ref "R18") (pin "1") (pinfunction "1_1") (pintype "passive"))
      (node (ref "R19") (pin "1") (pinfunction "1_1") (pintype "passive"))
      (node (ref "R2") (pin "2") (pinfunction "2_2") (pintype "passive"))
      (node (ref "R20") (pin "1") (pinfunction "1_1") (pintype "passive"))
      (node (ref "R22") (pin "1") (pinfunction "1_1") (pintype "passive"))
      (node (ref "R8") (pin "1") (pinfunction "1_1") (pintype "passive"))
      (node (ref "U3") (pin "17") (pinfunction "VCC_17") (pintype "power_in"))
      (node (ref "U3") (pin "27") (pinfunction "AVCC_27") (pintype "power_in"))
      (node (ref "U3") (pin "38") (pinfunction "VCC_38") (pintype "power_in"))
      (node (ref "U3") (pin "5") (pinfunction "VCC_5") (pintype "power_in"))
    )
    (net (code "79") (name "unconnected-(CN1-PadID)") (class "Default")
      (node (ref "CN1") (pin "ID") (pinfunction "ID_ID") (pintype "bidirectional"))
    )
    (net (code "80") (name "unconnected-(JP26-Pad6)") (class "Default")
      (node (ref "JP26") (pin "6") (pinfunction "6_6") (pintype "passive"))
    )
    (net (code "81") (name "unconnected-(JP27-Pad3)") (class "Default")
      (node (ref "JP27") (pin "3") (pinfunction "3_3") (pintype "passive"))
    )
    (net (code "82") (name "unconnected-(JP27-Pad5)") (class "Default")
      (node (ref "JP27") (pin "5") (pinfunction "5_5") (pintype "passive"))
    )
    (net (code "83") (name "unconnected-(JP28-Pad5)") (class "Default")
      (node (ref "JP28") (pin "5") (pinfunction "5_5") (pintype "passive"))
    )
    (net (code "84") (name "unconnected-(JP28-Pad6)") (class "Default")
      (node (ref "JP28") (pin "6") (pinfunction "6_6") (pintype "passive"))
    )
    (net (code "85") (name "unconnected-(JP28-Pad7)") (class "Default")
      (node (ref "JP28") (pin "7") (pinfunction "7_7") (pintype "passive"))
    )
    (net (code "86") (name "unconnected-(JP28-Pad9)") (class "Default")
      (node (ref "JP28") (pin "9") (pinfunction "9_9") (pintype "passive"))
    )
    (net (code "87") (name "unconnected-(JP28-Pad10)") (class "Default")
      (node (ref "JP28") (pin "10") (pinfunction "10_10") (pintype "passive"))
    )
    (net (code "88") (name "unconnected-(JP29-Pad5)") (class "Default")
      (node (ref "JP29") (pin "5") (pinfunction "5_5") (pintype "passive"))
    )
    (net (code "89") (name "unconnected-(JP29-Pad6)") (class "Default")
      (node (ref "JP29") (pin "6") (pinfunction "6_6") (pintype "passive"))
    )
  )
)
